# LED.net
KiCad netlist of a schematic drawn in Altium Designer
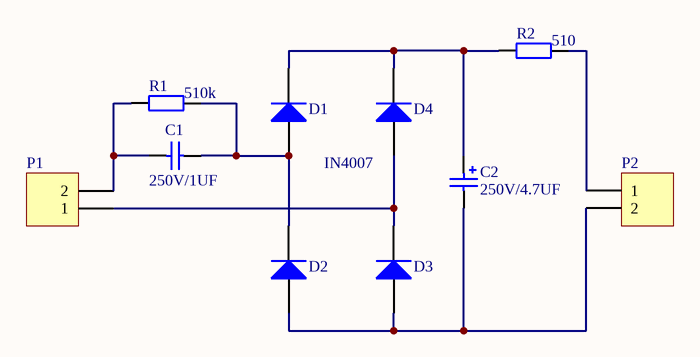
[diagram p0: LED节能灯电路模块.SchDoc]

(export (version "E")
  (design (tool "Eeschema 10.0.6"))
  (components
    (comp (ref "C1")
      (value "250V/1UF")
      (footprint "CP_CBB")
      (description "瓷片电容")
      (fields (field (name "PUBLISHER") "Altium Limited"))
      (libsource (lib "zxcourhc") (part "CPDR"))
    )
    (comp (ref "C2")
      (value "250V/4.7UF")
      (footprint "C-DJ-6")
      (description "电解电容")
      (fields (field (name "PUBLISHER") "Altium Limited"))
      (libsource (lib "zxcourhc") (part "DJDR"))
    )
    (comp (ref "D1")
      (value "IN4007")
      (footprint "D-ZL-10")
      (description "整流二极管")
      (fields (field (name "PUBLISHER") "Altium Limited"))
      (libsource (lib "zxcourhc") (part "ZL2JG"))
    )
    (comp (ref "D2")
      (value "IN4007")
      (footprint "D-ZL-10")
      (description "整流二极管")
      (fields (field (name "PUBLISHER") "Altium Limited"))
      (libsource (lib "zxcourhc") (part "ZL2JG"))
    )
    (comp (ref "D3")
      (value "IN4007")
      (footprint "D-ZL-10")
      (description "整流二极管")
      (fields (field (name "PUBLISHER") "Altium Limited"))
      (libsource (lib "zxcourhc") (part "ZL2JG"))
    )
    (comp (ref "D4")
      (value "IN4007")
      (footprint "D-ZL-10")
      (description "整流二极管")
      (fields (field (name "PUBLISHER") "Altium Limited"))
      (libsource (lib "zxcourhc") (part "ZL2JG"))
    )
    (comp (ref "P1")
      (value "PZ_2")
      (footprint "HDR-2")
      (description "排针——2")
      (fields (field (name "PUBLISHER") "Altium Limited"))
      (libsource (lib "") (part "PZ_2_1"))
    )
    (comp (ref "P2")
      (value "PZ_2")
      (footprint "HDR-2")
      (description "排针——2")
      (fields (field (name "PUBLISHER") "Altium Limited"))
      (libsource (lib "zxcourhc") (part "PZ_2"))
    )
    (comp (ref "R1")
      (value "510k")
      (footprint "AXIAL-0.4")
      (description "电阻")
      (fields (field (name "Comment") "Res") (field (name "PUBLISHER") "Altium Limited"))
      (libsource (lib "zxcourhc") (part "Res"))
    )
    (comp (ref "R2")
      (value "510")
      (footprint "AXIAL-0.4")
      (description "电阻")
      (fields (field (name "Comment") "Res") (field (name "PUBLISHER") "Altium Limited"))
      (libsource (lib "zxcourhc") (part "Res"))
    )
  )
  (nets
    (net (code "1") (name "Net-(C1-Pad1)") (class "Default")
      (node (ref "C1") (pin "1") (pinfunction "1_1") (pintype "passive"))
      (node (ref "P1") (pin "2") (pinfunction "2_2") (pintype "passive"))
      (node (ref "R1") (pin "1") (pinfunction "1_1") (pintype "passive"))
    )
    (net (code "2") (name "Net-(D1-A)") (class "Default")
      (node (ref "C1") (pin "2") (pinfunction "2_2") (pintype "passive"))
      (node (ref "D1") (pin "1") (pinfunction "A_1") (pintype "passive"))
      (node (ref "D2") (pin "2") (pinfunction "K_2") (pintype "passive"))
      (node (ref "R1") (pin "2") (pinfunction "2_2") (pintype "passive"))
    )
    (net (code "3") (name "Net-(D1-K)") (class "Default")
      (node (ref "C2") (pin "1") (pinfunction "1_1") (pintype "passive"))
      (node (ref "D1") (pin "2") (pinfunction "K_2") (pintype "passive"))
      (node (ref "D4") (pin "2") (pinfunction "K_2") (pintype "passive"))
      (node (ref "R2") (pin "1") (pinfunction "1_1") (pintype "passive"))
    )
    (net (code "4") (name "Net-(D2-A)") (class "Default")
      (node (ref "C2") (pin "2") (pinfunction "2_2") (pintype "passive"))
      (node (ref "D2") (pin "1") (pinfunction "A_1") (pintype "passive"))
      (node (ref "D3") (pin "1") (pinfunction "A_1") (pintype "passive"))
      (node (ref "P2") (pin "2") (pinfunction "2_2") (pintype "passive"))
    )
    (net (code "5") (name "Net-(D3-K)") (class "Default")
      (node (ref "D3") (pin "2") (pinfunction "K_2") (pintype "passive"))
      (node (ref "D4") (pin "1") (pinfunction "A_1") (pintype "passive"))
      (node (ref "P1") (pin "1") (pinfunction "1_1") (pintype "passive"))
    )
    (net (code "6") (name "Net-(P2-Pad1)") (class "Default")
      (node (ref "P2") (pin "1") (pinfunction "1_1") (pintype "passive"))
      (node (ref "R2") (pin "2") (pinfunction "2_2") (pintype "passive"))
    )
  )
)
